# USBC-UART.net
KiCad netlist of a schematic drawn in Altium Designer
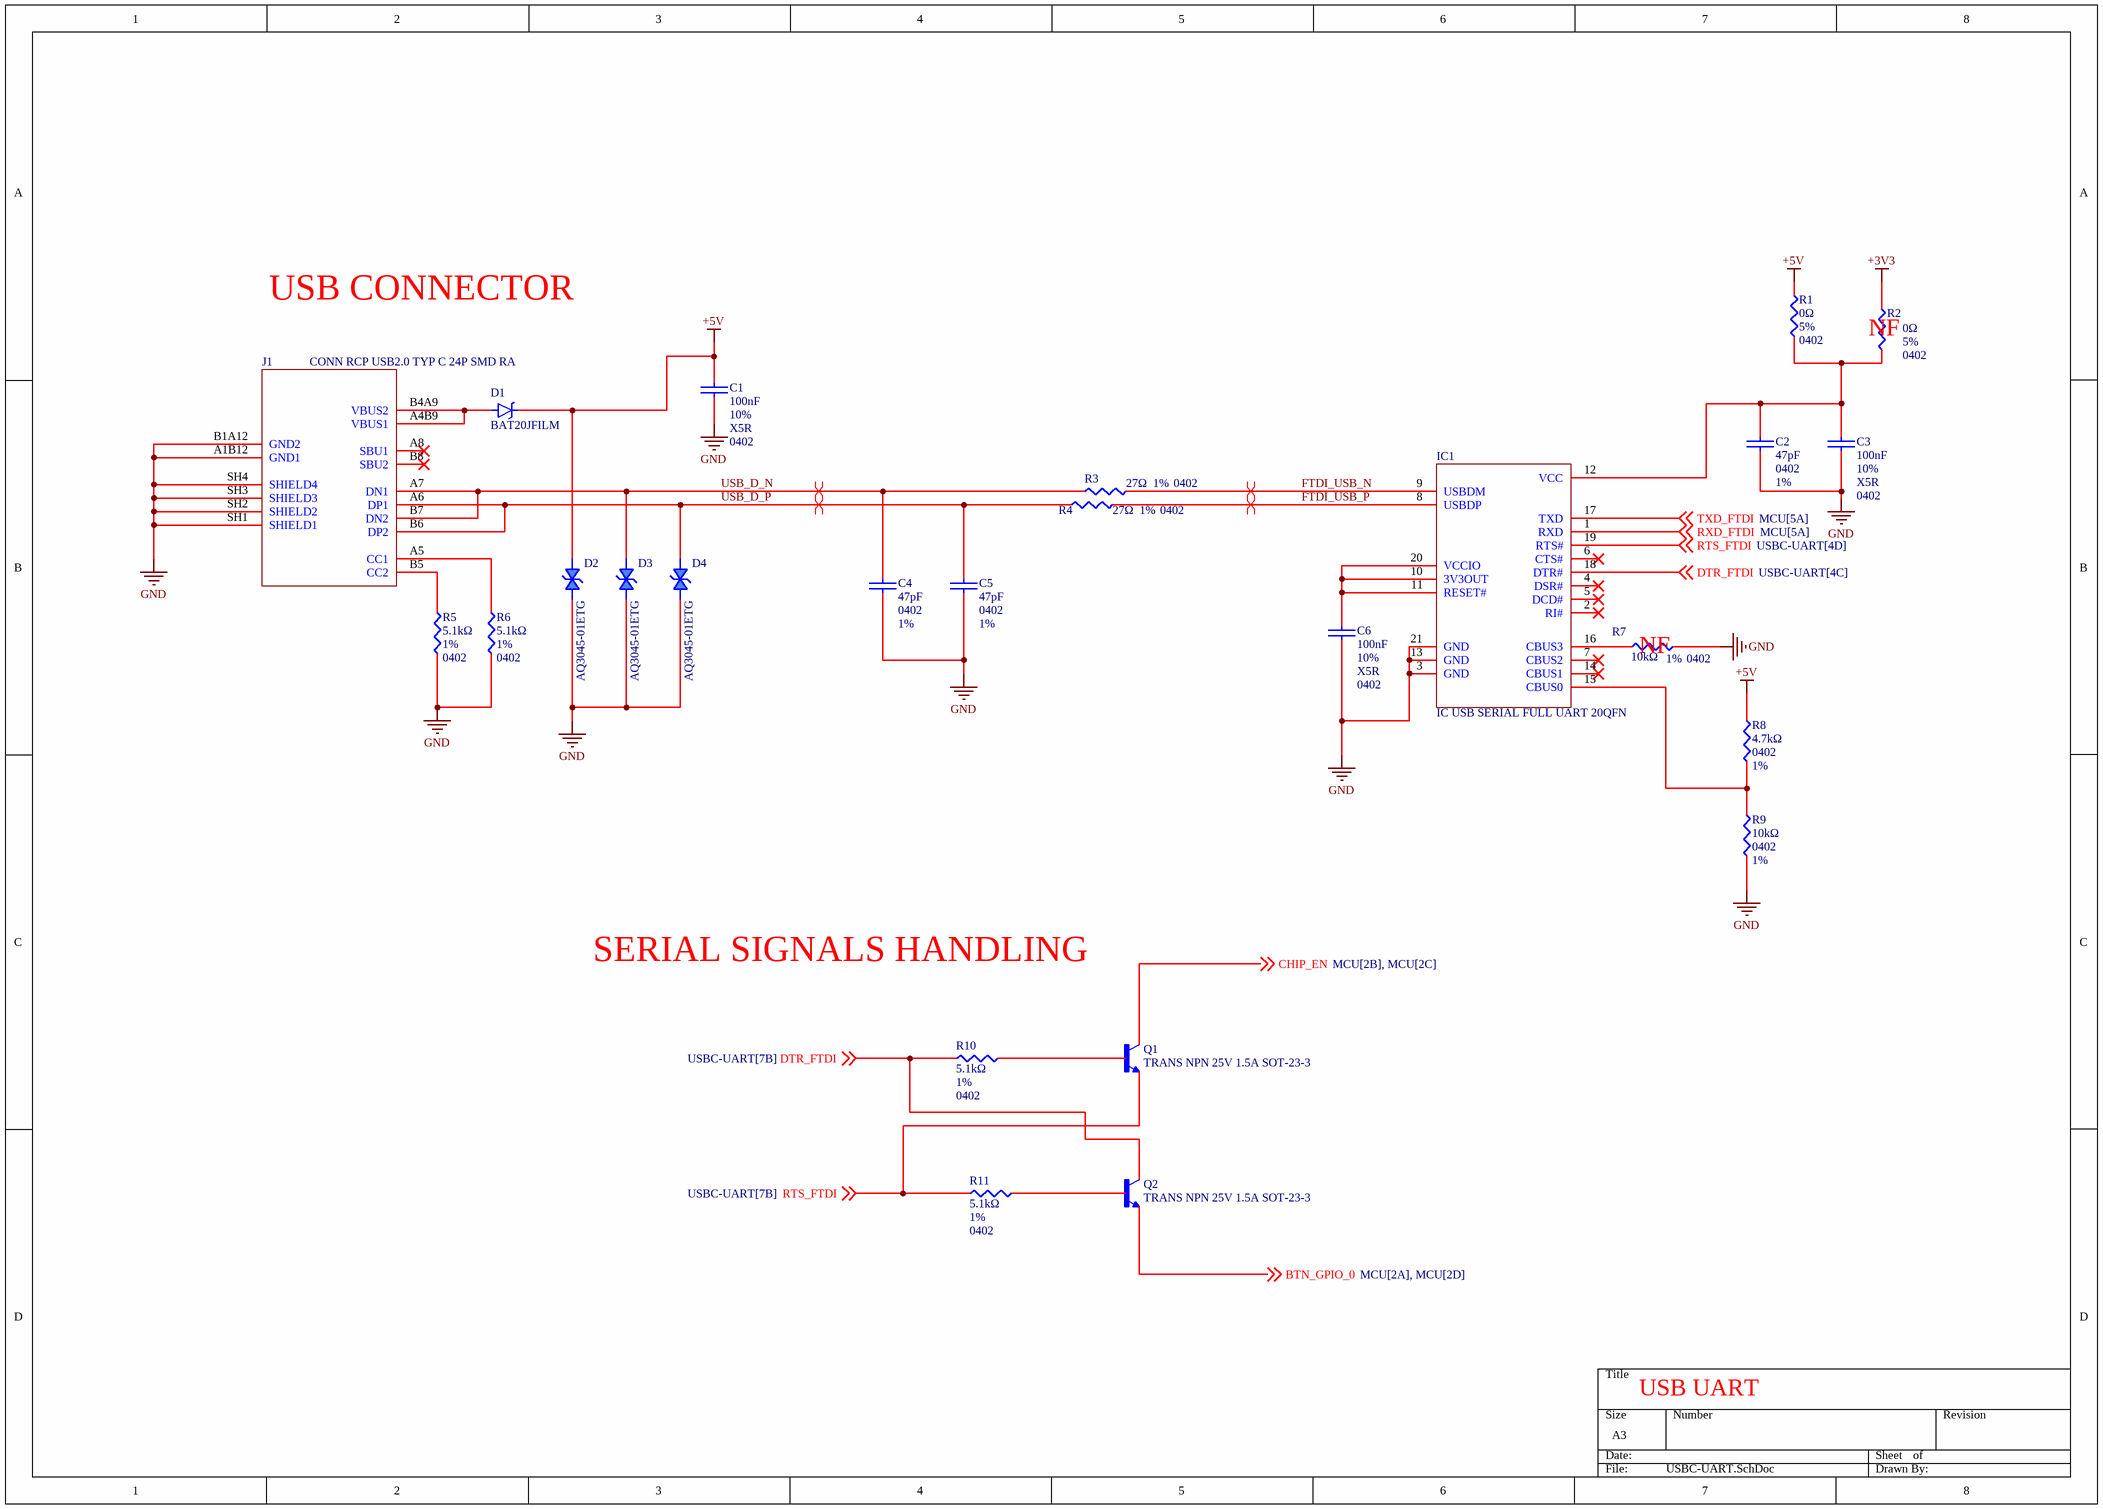
[diagram p0: USBC-UART.SchDoc]

(export (version "E")
  (design (tool "Eeschema 10.0.6"))
  (components
    (comp (ref "C1")
      (value "100nF")
      (footprint "C0402")
      (description "50V 100nF X5R ±10% 0402 Multilayer Ceramic Capacitors MLCC - SMD/SMT ROHS")
      (fields
        (field (name "MANUFACTURER") "Yageo Group")
        (field (name "MANUFACTURER PART NUMBER") "CC0402KRX5R9BB104")
        (field (name "TOLERANCE") "10%")
        (field (name "DIELECTRIC") "X5R")
        (field (name "CASE/PACKAGE") "0402")
      )
      (libsource (lib "Schlib") (part "CC0402KRX5R9BB104"))
    )
    (comp (ref "C2")
      (value "47pF")
      (footprint "C0402")
      (description "50V 47pF NP0 ±1% 0402 Multilayer Ceramic Capacitors MLCC - SMD/SMT ROHS")
      (fields
        (field (name "MANUFACTURER") "Yageo Group")
        (field (name "MANUFACTURER PART NUMBER") "CC0402FRNPO9BN470")
        (field (name "CASE/PACKAGE") "0402")
        (field (name "TOLERANCE") "1%")
      )
      (libsource (lib "Schlib") (part "CC0402FRNPO9BN470"))
    )
    (comp (ref "C3")
      (value "100nF")
      (footprint "C0402")
      (description "50V 100nF X5R ±10% 0402 Multilayer Ceramic Capacitors MLCC - SMD/SMT ROHS")
      (fields
        (field (name "MANUFACTURER") "Yageo Group")
        (field (name "MANUFACTURER PART NUMBER") "CC0402KRX5R9BB104")
        (field (name "TOLERANCE") "10%")
        (field (name "DIELECTRIC") "X5R")
        (field (name "CASE/PACKAGE") "0402")
      )
      (libsource (lib "Schlib") (part "CC0402KRX5R9BB104"))
    )
    (comp (ref "C4")
      (value "47pF")
      (footprint "C0402")
      (description "50V 47pF NP0 ±1% 0402 Multilayer Ceramic Capacitors MLCC - SMD/SMT ROHS")
      (fields
        (field (name "MANUFACTURER") "Yageo Group")
        (field (name "MANUFACTURER PART NUMBER") "CC0402FRNPO9BN470")
        (field (name "CASE/PACKAGE") "0402")
        (field (name "TOLERANCE") "1%")
      )
      (libsource (lib "Schlib") (part "CC0402FRNPO9BN470"))
    )
    (comp (ref "C5")
      (value "47pF")
      (footprint "C0402")
      (description "50V 47pF NP0 ±1% 0402 Multilayer Ceramic Capacitors MLCC - SMD/SMT ROHS")
      (fields
        (field (name "MANUFACTURER") "Yageo Group")
        (field (name "MANUFACTURER PART NUMBER") "CC0402FRNPO9BN470")
        (field (name "CASE/PACKAGE") "0402")
        (field (name "TOLERANCE") "1%")
      )
      (libsource (lib "Schlib") (part "CC0402FRNPO9BN470"))
    )
    (comp (ref "C6")
      (value "100nF")
      (footprint "C0402")
      (description "50V 100nF X5R ±10% 0402 Multilayer Ceramic Capacitors MLCC - SMD/SMT ROHS")
      (fields
        (field (name "MANUFACTURER") "Yageo Group")
        (field (name "MANUFACTURER PART NUMBER") "CC0402KRX5R9BB104")
        (field (name "TOLERANCE") "10%")
        (field (name "DIELECTRIC") "X5R")
        (field (name "CASE/PACKAGE") "0402")
      )
      (libsource (lib "Schlib") (part "CC0402KRX5R9BB104"))
    )
    (comp (ref "D1")
      (value "BAT20JFILM")
      (footprint "SOD-323")
      (description "BAT20J Series 23 V 1 A Surface Mount Switching Schottky Diode - SOD-323")
      (fields (field (name "MANUFACTURER") "STMicroelectronics") (field (name "LCSC PART") "C155590"))
      (libsource (lib "Schlib") (part "BAT20JFILM"))
    )
    (comp (ref "D2")
      (value "TVS DIODE 5.3VWM 12VC SOD882")
      (footprint "RTVS_SOD882_LTF-L")
      (description "Bi 30Kv 5V 0.35Pf Automotve Tvs Sod882/ T&r Rohs Compliant: Yes ¦Littelfuse AQ3045-01ETG")
      (fields
        (field (name "MANUFACTURER") "Littelfuse")
        (field (name "MANUFACTURER PART NUMBER") "AQ3045-01ETG")
      )
      (libsource (lib "Schlib") (part "AQ3045-01ETG"))
    )
    (comp (ref "D3")
      (value "TVS DIODE 5.3VWM 12VC SOD882")
      (footprint "RTVS_SOD882_LTF-L")
      (description "Bi 30Kv 5V 0.35Pf Automotve Tvs Sod882/ T&r Rohs Compliant: Yes ¦Littelfuse AQ3045-01ETG")
      (fields
        (field (name "MANUFACTURER") "Littelfuse")
        (field (name "MANUFACTURER PART NUMBER") "AQ3045-01ETG")
      )
      (libsource (lib "Schlib") (part "AQ3045-01ETG"))
    )
    (comp (ref "D4")
      (value "TVS DIODE 5.3VWM 12VC SOD882")
      (footprint "RTVS_SOD882_LTF-L")
      (description "Bi 30Kv 5V 0.35Pf Automotve Tvs Sod882/ T&r Rohs Compliant: Yes ¦Littelfuse AQ3045-01ETG")
      (fields
        (field (name "MANUFACTURER") "Littelfuse")
        (field (name "MANUFACTURER PART NUMBER") "AQ3045-01ETG")
      )
      (libsource (lib "Schlib") (part "AQ3045-01ETG"))
    )
    (comp (ref "IC1")
      (value "IC USB SERIAL FULL UART 20QFN")
      (footprint "QFN50P400X400X80-21N")
      (description "Tape & Reel (TR) 2006 UART USB 2.0 interface controller 3.3V~5V 4mm 8mA 12Mbps")
      (fields (field (name "MANUFACTURER") "FTDI") (field (name "MANUFACTURER PART NUMBER") "FT231XQ-R"))
      (libsource (lib "Schlib") (part "FT231XQ-R"))
    )
    (comp (ref "J1")
      (value "CONN RCP USB2.0 TYP C 24P SMD RA")
      (footprint "MOLEX_2171790001")
      (description "USB Connector, USB Type C, USB 2.0, Receptacle, 16 Ways, Surface Mount, Through Hole Mount")
      (fields (field (name "MANUFACTURER") "Molex") (field (name "MANUFACTURER PART NUMBER") "217179-0001"))
      (libsource (lib "Schlib") (part "217179-0001"))
    )
    (comp (ref "Q1")
      (value "TRANS NPN 25V 1.5A SOT-23-3")
      (footprint "TRANS_SS8050-G")
      (fields
        (field (name "MANUFACTURER") "Comchip")
        (field (name "MANUFACTURER PART NUMBER") "SS8050-G")
        (field (name "LCSC PART") "C3199946")
      )
      (libsource (lib "Schlib") (part "SS8050-G"))
    )
    (comp (ref "Q2")
      (value "TRANS NPN 25V 1.5A SOT-23-3")
      (footprint "TRANS_SS8050-G")
      (fields
        (field (name "MANUFACTURER") "Comchip")
        (field (name "MANUFACTURER PART NUMBER") "SS8050-G")
        (field (name "LCSC PART") "C3199946")
      )
      (libsource (lib "Schlib") (part "SS8050-G"))
    )
    (comp (ref "R1")
      (value "0Ω")
      (footprint "R0402")
      (description "GENERAL PURPOSE CHIP RESISTOR Metal Glaze/thick Film, 0.0625W, 0ohm, Surface Mount, 0402")
      (fields
        (field (name "MANUFACTURER") "Yageo Group")
        (field (name "MANUFACTURER PART NUMBER") "RC0402JR-070RL")
        (field (name "TOLERANCE") "5%")
        (field (name "CASE/PACKAGE") "0402")
      )
      (libsource (lib "Schlib") (part "RC0402JR-070RL"))
    )
    (comp (ref "R2")
      (value "0Ω")
      (footprint "R0402")
      (description "GENERAL PURPOSE CHIP RESISTOR Metal Glaze/thick Film, 0.0625W, 0ohm, Surface Mount, 0402")
      (fields
        (field (name "MANUFACTURER") "Yageo Group")
        (field (name "MANUFACTURER PART NUMBER") "RC0402JR-070RL")
        (field (name "TOLERANCE") "5%")
        (field (name "CASE/PACKAGE") "0402")
      )
      (libsource (lib "Schlib") (part "RC0402JR-070RL"))
    )
    (comp (ref "R3")
      (value "27Ω")
      (footprint "R0402")
      (description "62.5mW Thin Film Resistor ±50ppm/℃ ±1% 27Ω 0402 Chip Resistor - Surface Mount ROHS")
      (fields
        (field (name "MANUFACTURER") "Yageo Group")
        (field (name "MANUFACTURER PART NUMBER") "RT0402FRE0727RL")
        (field (name "TOLERANCE") "1%")
        (field (name "CASE/PACKAGE") "0402")
      )
      (libsource (lib "Schlib") (part "RT0402FRE0727RL"))
    )
    (comp (ref "R4")
      (value "27Ω")
      (footprint "R0402")
      (description "62.5mW Thin Film Resistor ±50ppm/℃ ±1% 27Ω 0402 Chip Resistor - Surface Mount ROHS")
      (fields
        (field (name "MANUFACTURER") "Yageo Group")
        (field (name "MANUFACTURER PART NUMBER") "RT0402FRE0727RL")
        (field (name "TOLERANCE") "1%")
        (field (name "CASE/PACKAGE") "0402")
      )
      (libsource (lib "Schlib") (part "RT0402FRE0727RL"))
    )
    (comp (ref "R5")
      (value "5.1kΩ")
      (footprint "R0402")
      (description "62.5mW Thick Film Resistors 50V ±100ppm/℃ ±1% 5.1kΩ 0402 Chip Resistor - Surface Mount ROHS")
      (fields
        (field (name "MANUFACTURER") "Yageo Group")
        (field (name "MANUFACTURER PART NUMBER") "RC0402FR-075K1L")
        (field (name "TOLERANCE") "1%")
        (field (name "CASE/PACKAGE") "0402")
      )
      (libsource (lib "Schlib") (part "RC0402FR-075K1L"))
    )
    (comp (ref "R6")
      (value "5.1kΩ")
      (footprint "R0402")
      (description "62.5mW Thick Film Resistors 50V ±100ppm/℃ ±1% 5.1kΩ 0402 Chip Resistor - Surface Mount ROHS")
      (fields
        (field (name "MANUFACTURER") "Yageo Group")
        (field (name "MANUFACTURER PART NUMBER") "RC0402FR-075K1L")
        (field (name "TOLERANCE") "1%")
        (field (name "CASE/PACKAGE") "0402")
      )
      (libsource (lib "Schlib") (part "RC0402FR-075K1L"))
    )
    (comp (ref "R7")
      (value "10kΩ")
      (footprint "R0402")
      (description "Chip Resistor with Ni/Au Terminations Thick Film 0402 10kOhm 1% Paper T/R")
      (fields
        (field (name "MANUFACTURER") "Yageo Group")
        (field (name "MANUFACTURER PART NUMBER") "AR0402FR-0710KL")
        (field (name "CASE/PACKAGE") "0402")
        (field (name "TOLERANCE") "1%")
      )
      (libsource (lib "Schlib") (part "AR0402FR-0710KL"))
    )
    (comp (ref "R8")
      (value "4.7kΩ")
      (footprint "R0402")
      (description "Chip Resistor with Ni/Au Terminations Thick Film 0402 4.7kOhm 1% Paper T/R")
      (fields
        (field (name "MANUFACTURER") "Yageo Group")
        (field (name "MANUFACTURER PART NUMBER") "AR0402FR-074K7L")
        (field (name "CASE/PACKAGE") "0402")
        (field (name "TOLERANCE") "1%")
      )
      (libsource (lib "Schlib") (part "AR0402FR-074K7L"))
    )
    (comp (ref "R9")
      (value "10kΩ")
      (footprint "R0402")
      (description "Chip Resistor with Ni/Au Terminations Thick Film 0402 10kOhm 1% Paper T/R")
      (fields
        (field (name "MANUFACTURER") "Yageo Group")
        (field (name "MANUFACTURER PART NUMBER") "AR0402FR-0710KL")
        (field (name "CASE/PACKAGE") "0402")
        (field (name "TOLERANCE") "1%")
      )
      (libsource (lib "Schlib") (part "AR0402FR-0710KL"))
    )
    (comp (ref "R10")
      (value "5.1kΩ")
      (footprint "R0402")
      (description "62.5mW Thick Film Resistors 50V ±100ppm/℃ ±1% 5.1kΩ 0402 Chip Resistor - Surface Mount ROHS")
      (fields
        (field (name "MANUFACTURER") "Yageo Group")
        (field (name "MANUFACTURER PART NUMBER") "RC0402FR-075K1L")
        (field (name "TOLERANCE") "1%")
        (field (name "CASE/PACKAGE") "0402")
      )
      (libsource (lib "Schlib") (part "RC0402FR-075K1L"))
    )
    (comp (ref "R11")
      (value "5.1kΩ")
      (footprint "R0402")
      (description "62.5mW Thick Film Resistors 50V ±100ppm/℃ ±1% 5.1kΩ 0402 Chip Resistor - Surface Mount ROHS")
      (fields
        (field (name "MANUFACTURER") "Yageo Group")
        (field (name "MANUFACTURER PART NUMBER") "RC0402FR-075K1L")
        (field (name "TOLERANCE") "1%")
        (field (name "CASE/PACKAGE") "0402")
      )
      (libsource (lib "Schlib") (part "RC0402FR-075K1L"))
    )
  )
  (nets
    (net (code "1") (name "+3V3") (class "Default")
      (node (ref "R2") (pin "2") (pinfunction "2_2") (pintype "passive"))
    )
    (net (code "2") (name "+5V") (class "Default")
      (node (ref "C1") (pin "2") (pinfunction "2_2") (pintype "passive"))
      (node (ref "D1") (pin "C") (pinfunction "C_C") (pintype "passive"))
      (node (ref "D2") (pin "2") (pinfunction "2_2") (pintype "passive"))
      (node (ref "R1") (pin "2") (pinfunction "2_2") (pintype "passive"))
      (node (ref "R8") (pin "2") (pinfunction "2_2") (pintype "passive"))
    )
    (net (code "3") (name "/FTDI_USB_N") (class "Default")
      (node (ref "IC1") (pin "9") (pinfunction "USBDM_9") (pintype "passive"))
      (node (ref "R3") (pin "2") (pinfunction "2_2") (pintype "passive"))
    )
    (net (code "4") (name "/FTDI_USB_P") (class "Default")
      (node (ref "IC1") (pin "8") (pinfunction "USBDP_8") (pintype "passive"))
      (node (ref "R4") (pin "2") (pinfunction "2_2") (pintype "passive"))
    )
    (net (code "5") (name "/USB_D_N") (class "Default")
      (node (ref "C4") (pin "2") (pinfunction "2_2") (pintype "passive"))
      (node (ref "D3") (pin "1") (pinfunction "1_1") (pintype "passive"))
      (node (ref "J1") (pin "A7") (pinfunction "DN1_A7") (pintype "passive"))
      (node (ref "J1") (pin "B7") (pinfunction "DN2_B7") (pintype "passive"))
      (node (ref "R3") (pin "1") (pinfunction "1_1") (pintype "passive"))
    )
    (net (code "6") (name "/USB_D_P") (class "Default")
      (node (ref "C5") (pin "2") (pinfunction "2_2") (pintype "passive"))
      (node (ref "D4") (pin "1") (pinfunction "1_1") (pintype "passive"))
      (node (ref "J1") (pin "A6") (pinfunction "DP1_A6") (pintype "passive"))
      (node (ref "J1") (pin "B6") (pinfunction "DP2_B6") (pintype "passive"))
      (node (ref "R4") (pin "1") (pinfunction "1_1") (pintype "passive"))
    )
    (net (code "7") (name "BTN_GPIO_0") (class "Default")
      (node (ref "Q2") (pin "2") (pinfunction "E_2") (pintype "passive"))
    )
    (net (code "8") (name "CHIP_EN") (class "Default")
      (node (ref "Q1") (pin "3") (pinfunction "C_3") (pintype "passive"))
    )
    (net (code "9") (name "DTR_FTDI") (class "Default")
      (node (ref "IC1") (pin "18") (pinfunction "DTR#_18") (pintype "passive"))
      (node (ref "Q2") (pin "3") (pinfunction "C_3") (pintype "passive"))
      (node (ref "R10") (pin "1") (pinfunction "1_1") (pintype "passive"))
    )
    (net (code "10") (name "GND") (class "Default")
      (node (ref "C1") (pin "1") (pinfunction "1_1") (pintype "passive"))
      (node (ref "C2") (pin "1") (pinfunction "1_1") (pintype "passive"))
      (node (ref "C3") (pin "1") (pinfunction "1_1") (pintype "passive"))
      (node (ref "C4") (pin "1") (pinfunction "1_1") (pintype "passive"))
      (node (ref "C5") (pin "1") (pinfunction "1_1") (pintype "passive"))
      (node (ref "C6") (pin "1") (pinfunction "1_1") (pintype "passive"))
      (node (ref "D2") (pin "1") (pinfunction "1_1") (pintype "passive"))
      (node (ref "D3") (pin "2") (pinfunction "2_2") (pintype "passive"))
      (node (ref "D4") (pin "2") (pinfunction "2_2") (pintype "passive"))
      (node (ref "IC1") (pin "13") (pinfunction "GND_13") (pintype "passive"))
      (node (ref "IC1") (pin "21") (pinfunction "GND_21") (pintype "passive"))
      (node (ref "IC1") (pin "3") (pinfunction "GND_3") (pintype "passive"))
      (node (ref "J1") (pin "A1B12") (pinfunction "GND1_A1B12") (pintype "passive"))
      (node (ref "J1") (pin "B1A12") (pinfunction "GND2_B1A12") (pintype "passive"))
      (node (ref "J1") (pin "SH1") (pinfunction "SHIELD1_SH1") (pintype "passive"))
      (node (ref "J1") (pin "SH2") (pinfunction "SHIELD2_SH2") (pintype "passive"))
      (node (ref "J1") (pin "SH3") (pinfunction "SHIELD3_SH3") (pintype "passive"))
      (node (ref "J1") (pin "SH4") (pinfunction "SHIELD4_SH4") (pintype "passive"))
      (node (ref "R5") (pin "2") (pinfunction "2_2") (pintype "passive"))
      (node (ref "R6") (pin "2") (pinfunction "2_2") (pintype "passive"))
      (node (ref "R7") (pin "1") (pinfunction "1_1") (pintype "passive"))
      (node (ref "R9") (pin "1") (pinfunction "1_1") (pintype "passive"))
    )
    (net (code "11") (name "Net-(IC1-3V3OUT)") (class "Default")
      (node (ref "C6") (pin "2") (pinfunction "2_2") (pintype "passive"))
      (node (ref "IC1") (pin "10") (pinfunction "3V3OUT_10") (pintype "passive"))
      (node (ref "IC1") (pin "11") (pinfunction "RESET#_11") (pintype "passive"))
      (node (ref "IC1") (pin "20") (pinfunction "VCCIO_20") (pintype "passive"))
    )
    (net (code "12") (name "Net-(IC1-CBUS0)") (class "Default")
      (node (ref "IC1") (pin "15") (pinfunction "CBUS0_15") (pintype "passive"))
      (node (ref "R8") (pin "1") (pinfunction "1_1") (pintype "passive"))
      (node (ref "R9") (pin "2") (pinfunction "2_2") (pintype "passive"))
    )
    (net (code "13") (name "Net-(IC1-CBUS3)") (class "Default")
      (node (ref "IC1") (pin "16") (pinfunction "CBUS3_16") (pintype "passive"))
      (node (ref "R7") (pin "2") (pinfunction "2_2") (pintype "passive"))
    )
    (net (code "14") (name "Net-(IC1-VCC)") (class "Default")
      (node (ref "C2") (pin "2") (pinfunction "2_2") (pintype "passive"))
      (node (ref "C3") (pin "2") (pinfunction "2_2") (pintype "passive"))
      (node (ref "IC1") (pin "12") (pinfunction "VCC_12") (pintype "passive"))
      (node (ref "R1") (pin "1") (pinfunction "1_1") (pintype "passive"))
      (node (ref "R2") (pin "1") (pinfunction "1_1") (pintype "passive"))
    )
    (net (code "15") (name "Net-(J1-CC1)") (class "Default")
      (node (ref "J1") (pin "A5") (pinfunction "CC1_A5") (pintype "passive"))
      (node (ref "R6") (pin "1") (pinfunction "1_1") (pintype "passive"))
    )
    (net (code "16") (name "Net-(J1-CC2)") (class "Default")
      (node (ref "J1") (pin "B5") (pinfunction "CC2_B5") (pintype "passive"))
      (node (ref "R5") (pin "1") (pinfunction "1_1") (pintype "passive"))
    )
    (net (code "17") (name "Net-(J1-VBUS1)") (class "Default")
      (node (ref "D1") (pin "A") (pinfunction "A_A") (pintype "passive"))
      (node (ref "J1") (pin "A4B9") (pinfunction "VBUS1_A4B9") (pintype "passive"))
      (node (ref "J1") (pin "B4A9") (pinfunction "VBUS2_B4A9") (pintype "passive"))
    )
    (net (code "18") (name "Net-(Q1-B)") (class "Default")
      (node (ref "Q1") (pin "1") (pinfunction "B_1") (pintype "passive"))
      (node (ref "R10") (pin "2") (pinfunction "2_2") (pintype "passive"))
    )
    (net (code "19") (name "Net-(Q2-B)") (class "Default")
      (node (ref "Q2") (pin "1") (pinfunction "B_1") (pintype "passive"))
      (node (ref "R11") (pin "2") (pinfunction "2_2") (pintype "passive"))
    )
    (net (code "20") (name "RTS_FTDI") (class "Default")
      (node (ref "IC1") (pin "19") (pinfunction "RTS#_19") (pintype "passive"))
      (node (ref "Q1") (pin "2") (pinfunction "E_2") (pintype "passive"))
      (node (ref "R11") (pin "1") (pinfunction "1_1") (pintype "passive"))
    )
    (net (code "21") (name "RXD_FTDI") (class "Default")
      (node (ref "IC1") (pin "1") (pinfunction "RXD_1") (pintype "passive"))
    )
    (net (code "22") (name "TXD_FTDI") (class "Default")
      (node (ref "IC1") (pin "17") (pinfunction "TXD_17") (pintype "passive"))
    )
    (net (code "23") (name "unconnected-(IC1-CBUS1-Pad14)") (class "Default")
      (node (ref "IC1") (pin "14") (pinfunction "CBUS1_14") (pintype "passive+no_connect"))
    )
    (net (code "24") (name "unconnected-(IC1-CBUS2-Pad7)") (class "Default")
      (node (ref "IC1") (pin "7") (pinfunction "CBUS2_7") (pintype "passive+no_connect"))
    )
    (net (code "25") (name "unconnected-(IC1-CTS#-Pad6)") (class "Default")
      (node (ref "IC1") (pin "6") (pinfunction "CTS#_6") (pintype "passive+no_connect"))
    )
    (net (code "26") (name "unconnected-(IC1-DCD#-Pad5)") (class "Default")
      (node (ref "IC1") (pin "5") (pinfunction "DCD#_5") (pintype "passive+no_connect"))
    )
    (net (code "27") (name "unconnected-(IC1-DSR#-Pad4)") (class "Default")
      (node (ref "IC1") (pin "4") (pinfunction "DSR#_4") (pintype "passive+no_connect"))
    )
    (net (code "28") (name "unconnected-(IC1-RI#-Pad2)") (class "Default")
      (node (ref "IC1") (pin "2") (pinfunction "RI#_2") (pintype "passive+no_connect"))
    )
    (net (code "29") (name "unconnected-(J1-SBU1-PadA8)") (class "Default")
      (node (ref "J1") (pin "A8") (pinfunction "SBU1_A8") (pintype "passive+no_connect"))
    )
    (net (code "30") (name "unconnected-(J1-SBU2-PadB8)") (class "Default")
      (node (ref "J1") (pin "B8") (pinfunction "SBU2_B8") (pintype "passive+no_connect"))
    )
  )
)
